# TCAN1146_PWR_MGMT.net
KiCad netlist of a schematic drawn in Altium Designer
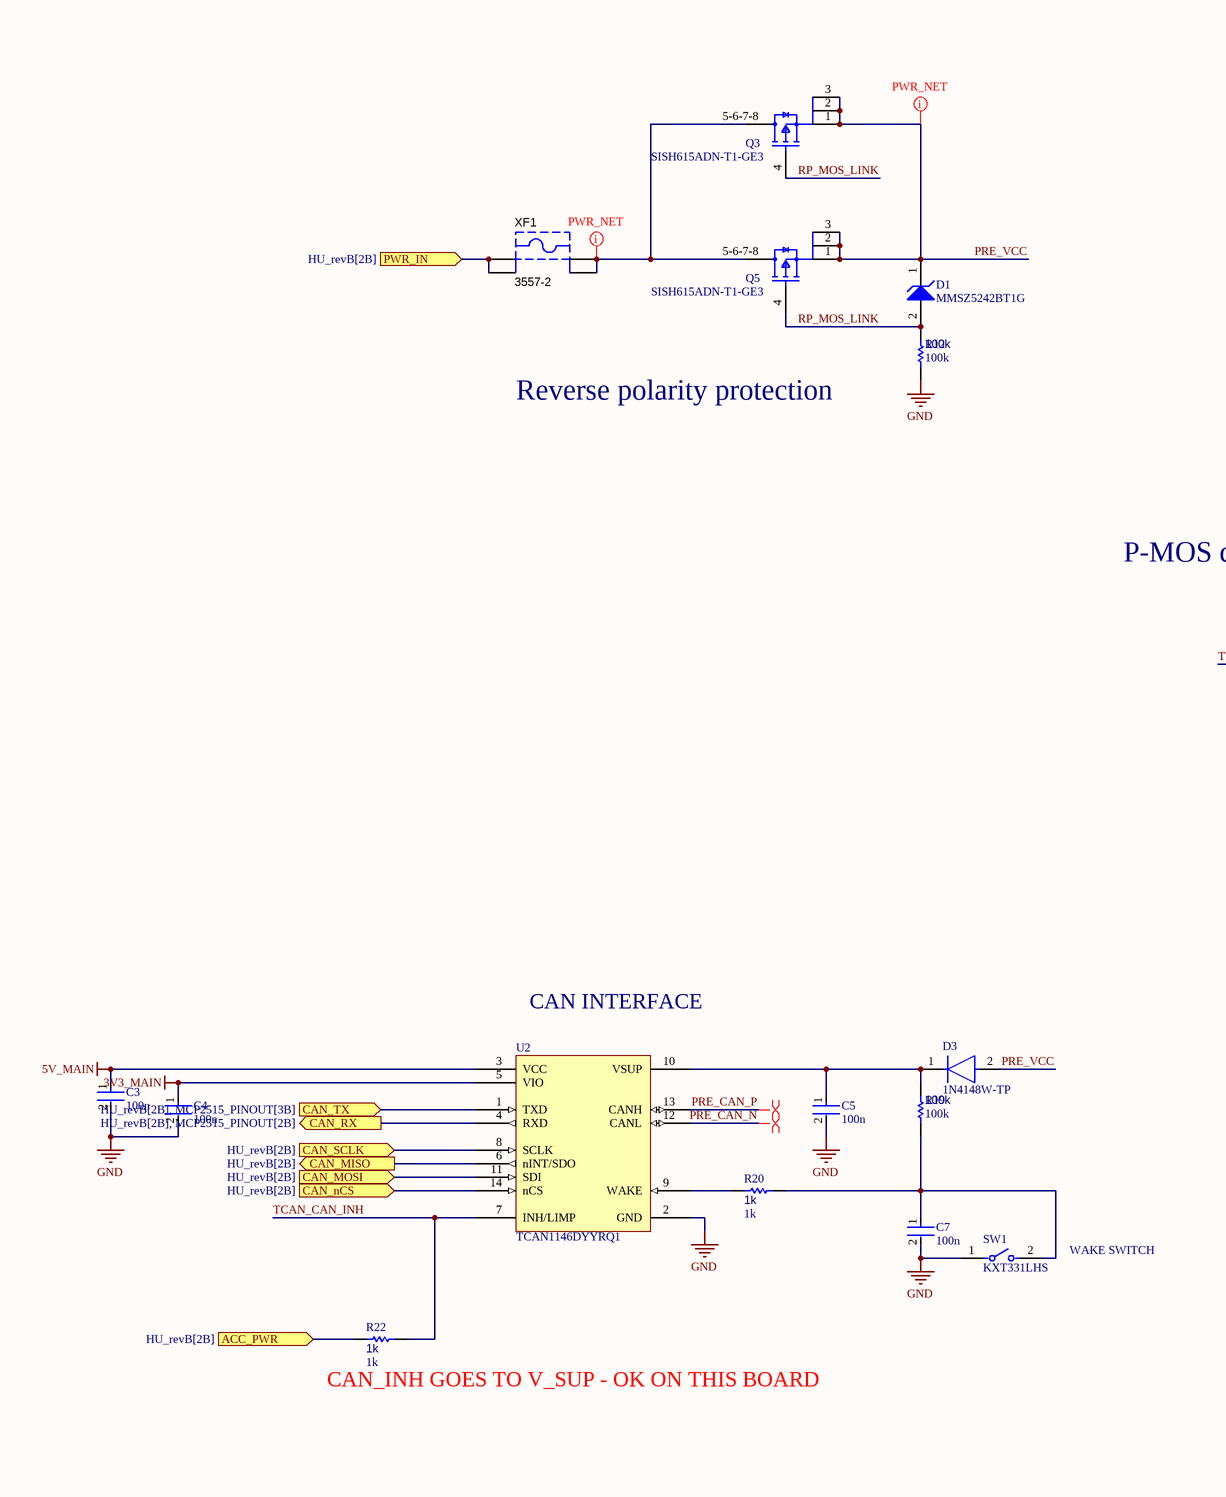
[diagram p0: TCAN1146_PWR_MGMT.SchDoc, left]
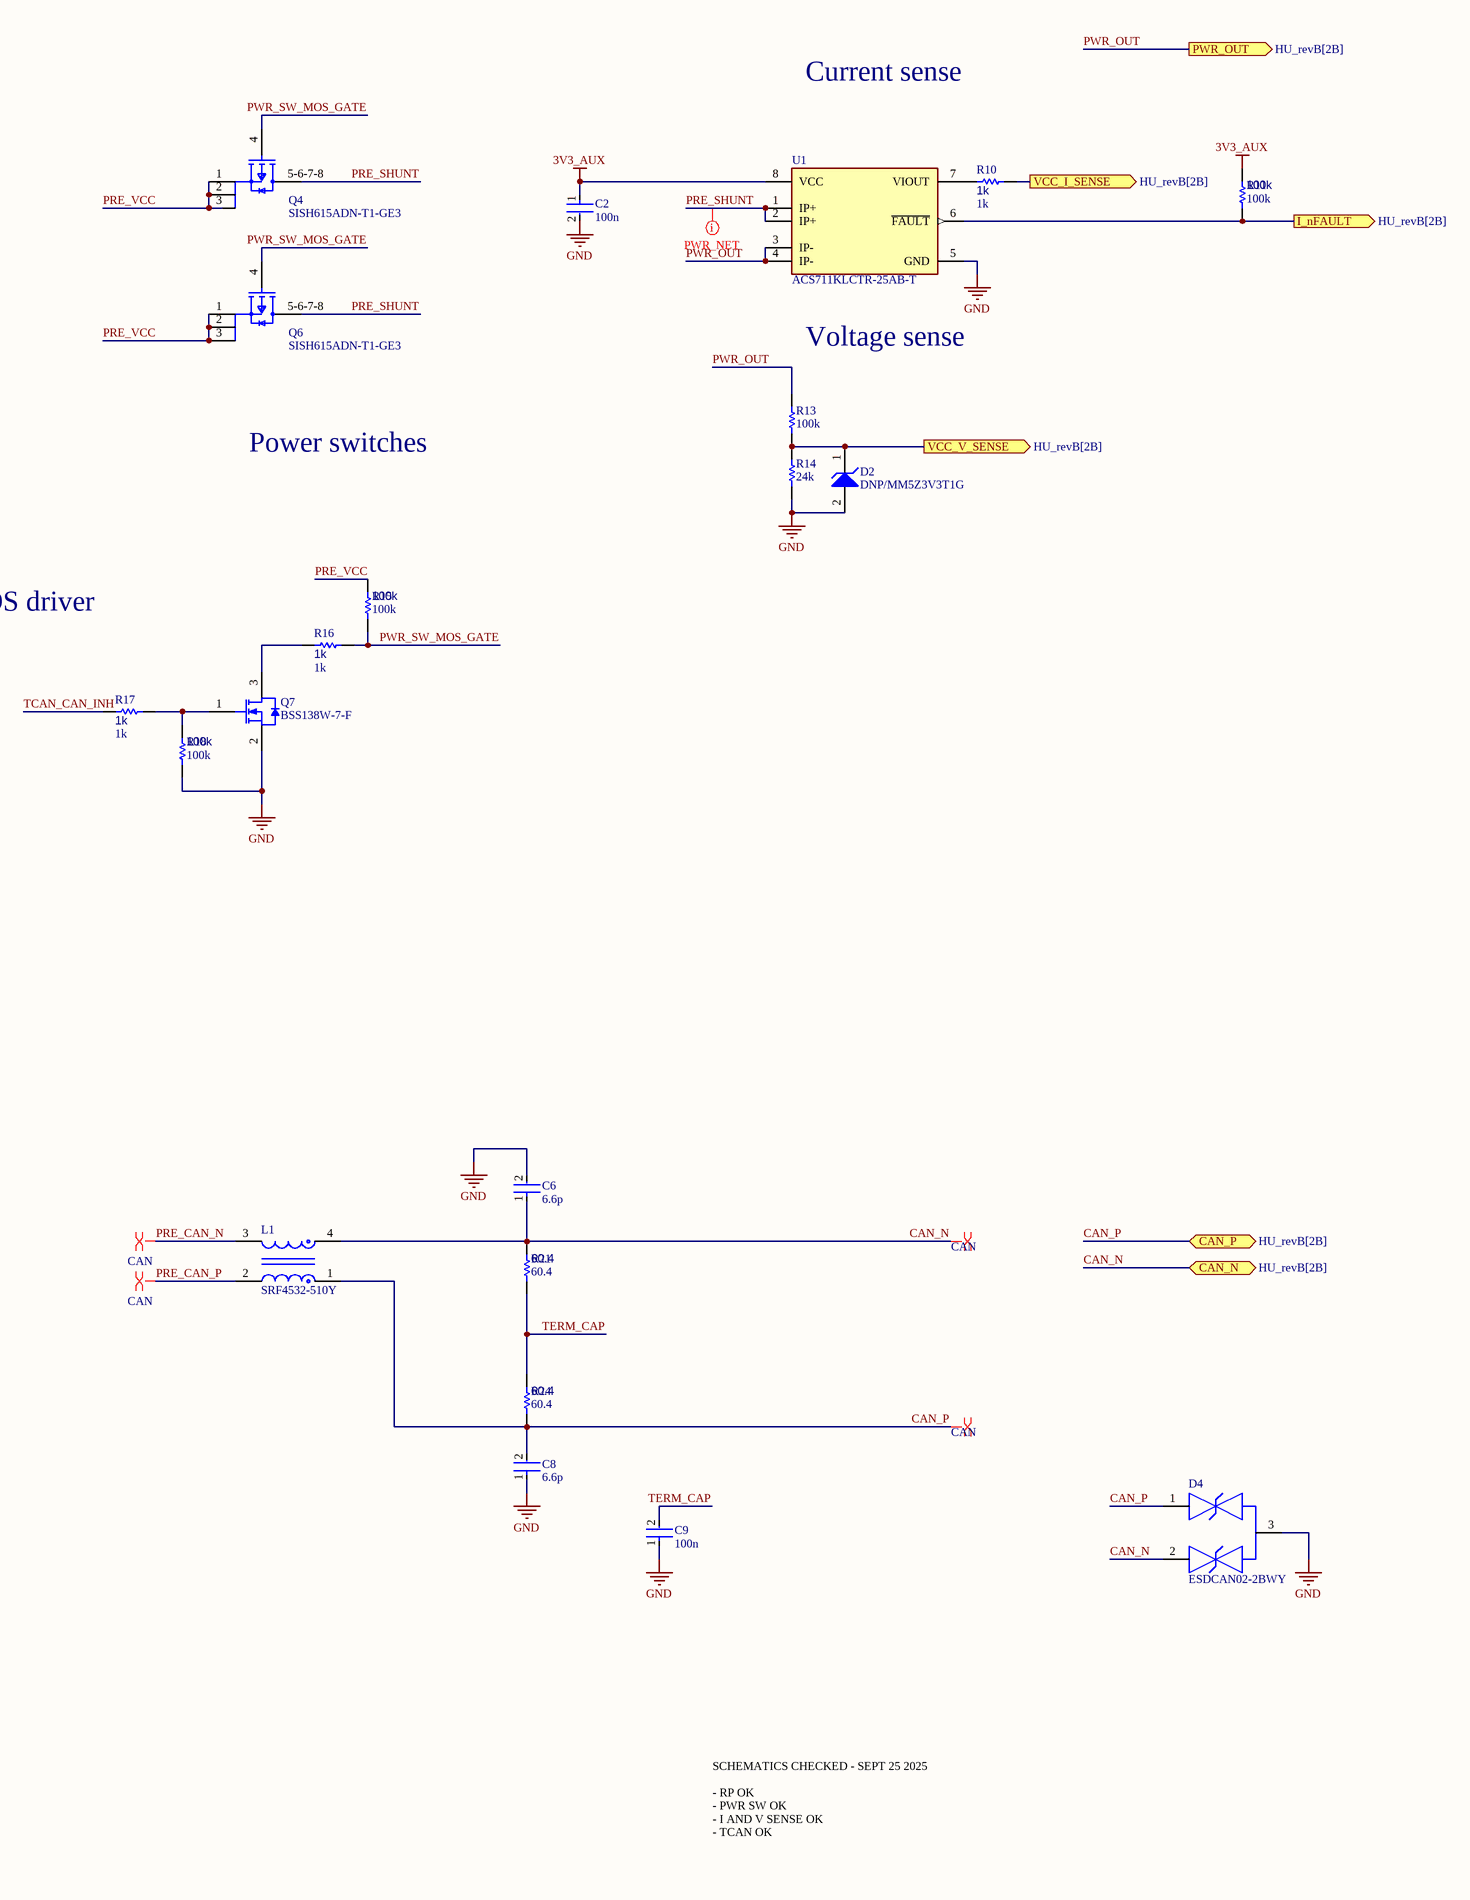
[diagram p1: TCAN1146_PWR_MGMT.SchDoc, right]

(export (version "E")
  (design (tool "Eeschema 10.0.6"))
  (components
    (comp (ref "C2")
      (value "100n")
      (footprint "FP-0402-L_1_0_0_05-W_0_5-IPC_A")
      (description "LARGE PADS, 0402 CAP, CHANGE COMMENT TO MATCH REAL P/N")
      (libsource (lib "Space Concordia") (part "b4654b650e69147ec39a6b967a45e02"))
    )
    (comp (ref "C3")
      (value "100n")
      (footprint "FP-0402-L_1_0_0_05-W_0_5-IPC_A")
      (description "LARGE PADS, 0402 CAP, CHANGE COMMENT TO MATCH REAL P/N")
      (libsource (lib "Space Concordia") (part "b4654b650e69147ec39a6b967a45e02"))
    )
    (comp (ref "C4")
      (value "100n")
      (footprint "FP-0402-L_1_0_0_05-W_0_5-IPC_A")
      (description "LARGE PADS, 0402 CAP, CHANGE COMMENT TO MATCH REAL P/N")
      (libsource (lib "Space Concordia") (part "b4654b650e69147ec39a6b967a45e02"))
    )
    (comp (ref "C5")
      (value "100n")
      (footprint "FP-0402-L_1_0_0_05-W_0_5-IPC_A")
      (description "LARGE PADS, 0402 CAP, CHANGE COMMENT TO MATCH REAL P/N")
      (libsource (lib "Space Concordia") (part "b4654b650e69147ec39a6b967a45e02"))
    )
    (comp (ref "C6")
      (value "6.6p")
      (footprint "FP-0402-L_1_0_0_05-W_0_5-IPC_A")
      (description "LARGE PADS, 0402 CAP, CHANGE COMMENT TO MATCH REAL P/N")
      (libsource (lib "Space Concordia") (part "b4654b650e69147ec39a6b967a45e02"))
    )
    (comp (ref "C7")
      (value "100n")
      (footprint "FP-0402-L_1_0_0_05-W_0_5-IPC_A")
      (description "LARGE PADS, 0402 CAP, CHANGE COMMENT TO MATCH REAL P/N")
      (libsource (lib "Space Concordia") (part "b4654b650e69147ec39a6b967a45e02"))
    )
    (comp (ref "C8")
      (value "6.6p")
      (footprint "FP-0402-L_1_0_0_05-W_0_5-IPC_A")
      (description "LARGE PADS, 0402 CAP, CHANGE COMMENT TO MATCH REAL P/N")
      (libsource (lib "Space Concordia") (part "b4654b650e69147ec39a6b967a45e02"))
    )
    (comp (ref "C9")
      (value "100n")
      (footprint "FP-0402-L_1_0_0_05-W_0_5-IPC_A")
      (description "LARGE PADS, 0402 CAP, CHANGE COMMENT TO MATCH REAL P/N")
      (libsource (lib "Space Concordia") (part "b4654b650e69147ec39a6b967a45e02"))
    )
    (comp (ref "D1")
      (value "MMSZ5242BT1G")
      (footprint "ONSC-SOD-123-2-425-04_V")
      (description "Zener Voltage Regulator, 500 mW, 2-Pin SOD-123, Pb-Free, Tape and Reel")
      (fields (field (name "MANUFACTURER") "On Semiconductor"))
      (libsource (lib "Altium Content Vault") (part "ONSC-K1A2-2"))
    )
    (comp (ref "D2")
      (value "DNP/MM5Z3V3T1G")
      (footprint "ONSC-SOD-523-2-502-01_V")
      (description "Zener Voltage Regulator, 500 mW, 2-Pin SOD-523, Pb-Free, Tape and Reel")
      (fields (field (name "MANUFACTURER") "On Semiconductor") (field (name "PARTNUMBER") "MM5Z3V3T1G"))
      (libsource (lib "Altium Content Vault") (part "ONSC-K1A2-2"))
    )
    (comp (ref "D3")
      (value "1N4148W-TP")
      (footprint "FP-SOD-123-IPC_A")
      (description "DIODE GEN PURP 100V 150MA SOD123")
      (libsource (lib "Altium Content Vault") (part "d7152d700b627762746794eb795d46e"))
    )
    (comp (ref "D4")
      (value "ESDCAN02-2BWY")
      (footprint "FP-SOT323-3L-MFG")
      (description "TVS DIODE 26.5V 44V SOT323-3")
      (fields
        (field (name "MANUFACTURER") "STMicroelectronics")
        (field (name "OCTOPART") "https://octopart.com/esdcan02-2bwy-stmicroelectronics-58631133")
      )
      (libsource (lib "Altium Content Vault") (part "0b9019fb5e52ed66df21ec1535be59d"))
    )
    (comp (ref "L1")
      (value "SRF4532-510Y")
      (footprint "FP-SRF4532-MFG")
      (description "CMC 51UH 200MA 2LN 2KOHM SMD")
      (fields (field (name "TOLERANCE") "50%"))
      (libsource (lib "Altium Content Vault") (part "aca3f6a10b859f211cca95010157f3b"))
    )
    (comp (ref "Q3")
      (value "SISH615ADN-T1-GE3")
      (footprint "SISH615ADN-T1-GE3-Footprint-1")
      (description "Trans MOSFET P-CH 20V 22.1A 8-Pin PowerPAK 1212 EP T/R")
      (libsource (lib "Space Concordia") (part "CMP-013-00036-4"))
    )
    (comp (ref "Q4")
      (value "SISH615ADN-T1-GE3")
      (footprint "SISH615ADN-T1-GE3-Footprint-1")
      (description "Trans MOSFET P-CH 20V 22.1A 8-Pin PowerPAK 1212 EP T/R")
      (libsource (lib "Space Concordia") (part "CMP-013-00036-4"))
    )
    (comp (ref "Q5")
      (value "SISH615ADN-T1-GE3")
      (footprint "SISH615ADN-T1-GE3-Footprint-1")
      (description "Trans MOSFET P-CH 20V 22.1A 8-Pin PowerPAK 1212 EP T/R")
      (libsource (lib "Space Concordia") (part "CMP-013-00036-4"))
    )
    (comp (ref "Q6")
      (value "SISH615ADN-T1-GE3")
      (footprint "SISH615ADN-T1-GE3-Footprint-1")
      (description "Trans MOSFET P-CH 20V 22.1A 8-Pin PowerPAK 1212 EP T/R")
      (libsource (lib "Space Concordia") (part "CMP-013-00036-4"))
    )
    (comp (ref "Q7")
      (value "BSS138W-7-F")
      (footprint "DIOD-SOT323-3_V")
      (fields (field (name "MANUFACTURER") "DiodesIncorporated"))
      (libsource (lib "Altium Content Vault") (part "NEMOS-GSD-3"))
    )
    (comp (ref "R10")
      (value "1k")
      (footprint "R0603B")
      (description "Resistor")
      (fields (field (name "ALTIUM_VALUE") "1k"))
      (libsource (lib "Space Concordia") (part "Resistor"))
    )
    (comp (ref "R11")
      (value "100k")
      (footprint "R0603B")
      (description "Resistor")
      (fields (field (name "ALTIUM_VALUE") "100k"))
      (libsource (lib "Space Concordia") (part "Resistor"))
    )
    (comp (ref "R12")
      (value "100k")
      (footprint "R0603B")
      (description "Resistor")
      (fields (field (name "ALTIUM_VALUE") "100k"))
      (libsource (lib "Space Concordia") (part "Resistor"))
    )
    (comp (ref "R13")
      (value "100k")
      (footprint "R0603B")
      (description "Resistor")
      (libsource (lib "Space Concordia") (part "Resistor"))
    )
    (comp (ref "R14")
      (value "24k")
      (footprint "R0603B")
      (description "Resistor")
      (libsource (lib "Space Concordia") (part "Resistor"))
    )
    (comp (ref "R15")
      (value "100k")
      (footprint "R0603B")
      (description "Resistor")
      (fields (field (name "ALTIUM_VALUE") "100k"))
      (libsource (lib "Space Concordia") (part "Resistor"))
    )
    (comp (ref "R16")
      (value "1k")
      (footprint "R0603B")
      (description "Resistor")
      (fields (field (name "ALTIUM_VALUE") "1k"))
      (libsource (lib "Space Concordia") (part "Resistor"))
    )
    (comp (ref "R17")
      (value "1k")
      (footprint "R0603B")
      (description "Resistor")
      (fields (field (name "ALTIUM_VALUE") "1k"))
      (libsource (lib "Space Concordia") (part "Resistor"))
    )
    (comp (ref "R18")
      (value "100k")
      (footprint "R0603B")
      (description "Resistor")
      (fields (field (name "ALTIUM_VALUE") "100k"))
      (libsource (lib "Space Concordia") (part "Resistor"))
    )
    (comp (ref "R19")
      (value "100k")
      (footprint "R0603B")
      (description "Resistor")
      (fields (field (name "ALTIUM_VALUE") "100k"))
      (libsource (lib "Space Concordia") (part "Resistor"))
    )
    (comp (ref "R20")
      (value "1k")
      (footprint "R0603B")
      (description "Resistor")
      (fields (field (name "ALTIUM_VALUE") "1k"))
      (libsource (lib "Space Concordia") (part "Resistor"))
    )
    (comp (ref "R21")
      (value "60.4")
      (footprint "R0603B")
      (description "Resistor")
      (fields (field (name "ALTIUM_VALUE") "60.4"))
      (libsource (lib "Space Concordia") (part "Resistor"))
    )
    (comp (ref "R22")
      (value "1k")
      (footprint "R0603B")
      (description "Resistor")
      (fields (field (name "ALTIUM_VALUE") "1k"))
      (libsource (lib "Space Concordia") (part "Resistor"))
    )
    (comp (ref "R24")
      (value "60.4")
      (footprint "R0603B")
      (description "Resistor")
      (fields (field (name "ALTIUM_VALUE") "60.4"))
      (libsource (lib "Space Concordia") (part "Resistor"))
    )
    (comp (ref "SW1")
      (value "KXT331LHS")
      (footprint "FP-KXT331LHS-MFG")
      (description "SWITCH TACTILE SPST-NO 0.02A 15V")
      (libsource (lib "Altium Content Vault") (part "bb27bde45df87f1f469753f287ef5ae"))
    )
    (comp (ref "U1")
      (value "ACS711KLCTR-25AB-T")
      (footprint "FP-LC-8-IPC_A")
      (description "SENSOR CURRENT HALL 25A AC/DC")
      (libsource (lib "Altium Content Vault") (part "eeba3158841281b4ae542a6e24976ab"))
    )
    (comp (ref "U2")
      (value "TCAN1146DYYRQ1")
      (footprint "TCAN1146DYYRQ1-Footprint-1")
      (libsource (lib "Space Concordia") (part "CMP-015-00012-2"))
    )
    (comp (ref "XF1")
      (value "3557-2")
      (footprint "KSTN-3557-2")
      (description "FUSE HOLDER, PCB MOUNT, 500VAC, 20A, ROHS")
      (fields (field (name "VOLTAGE") "500V") (field (name "MANUFACTURER") "Keystone-Electronics"))
      (libsource (lib "Altium Content Vault") (part "FUSE_HOLDER-4"))
    )
  )
  (nets
    (net (code "1") (name "/ACC_PWR") (class "Default")
      (node (ref "R22") (pin "1") (pinfunction "1_1") (pintype "passive"))
    )
    (net (code "2") (name "/CAN_MISO") (class "Default")
      (node (ref "U2") (pin "6") (pinfunction "nINT/SDO_6") (pintype "output"))
    )
    (net (code "3") (name "/CAN_MOSI") (class "Default")
      (node (ref "U2") (pin "11") (pinfunction "SDI_11") (pintype "input"))
    )
    (net (code "4") (name "/CAN_N") (class "Default")
      (node (ref "C6") (pin "1") (pinfunction "1_1") (pintype "passive"))
      (node (ref "D4") (pin "2") (pinfunction "2_2") (pintype "passive"))
      (node (ref "L1") (pin "4") (pinfunction "4_4") (pintype "passive"))
      (node (ref "R21") (pin "2") (pinfunction "2_2") (pintype "passive"))
    )
    (net (code "5") (name "/CAN_P") (class "Default")
      (node (ref "C8") (pin "2") (pinfunction "2_2") (pintype "passive"))
      (node (ref "D4") (pin "1") (pinfunction "1_1") (pintype "passive"))
      (node (ref "L1") (pin "1") (pinfunction "1_1") (pintype "passive"))
      (node (ref "R24") (pin "1") (pinfunction "1_1") (pintype "passive"))
    )
    (net (code "6") (name "/CAN_RX") (class "Default")
      (node (ref "U2") (pin "4") (pinfunction "RXD_4") (pintype "output"))
    )
    (net (code "7") (name "/CAN_SCLK") (class "Default")
      (node (ref "U2") (pin "8") (pinfunction "SCLK_8") (pintype "input"))
    )
    (net (code "8") (name "/CAN_TX") (class "Default")
      (node (ref "U2") (pin "1") (pinfunction "TXD_1") (pintype "input"))
    )
    (net (code "9") (name "/CAN_nCS") (class "Default")
      (node (ref "U2") (pin "14") (pinfunction "nCS_14") (pintype "input"))
    )
    (net (code "10") (name "/I_nFAULT") (class "Default")
      (node (ref "R11") (pin "1") (pinfunction "1_1") (pintype "passive"))
      (node (ref "U1") (pin "6") (pinfunction "~{FAULT}_6") (pintype "output"))
    )
    (net (code "11") (name "/PRE_CAN_N") (class "Default")
      (node (ref "L1") (pin "3") (pinfunction "3_3") (pintype "passive"))
      (node (ref "U2") (pin "12") (pinfunction "CANL_12") (pintype "bidirectional"))
    )
    (net (code "12") (name "/PRE_CAN_P") (class "Default")
      (node (ref "L1") (pin "2") (pinfunction "2_2") (pintype "passive"))
      (node (ref "U2") (pin "13") (pinfunction "CANH_13") (pintype "bidirectional"))
    )
    (net (code "13") (name "/PRE_SHUNT") (class "Default")
      (node (ref "Q4") (pin "5-6-7-8") (pinfunction "D_5-6-7-8") (pintype "passive"))
      (node (ref "Q6") (pin "5-6-7-8") (pinfunction "D_5-6-7-8") (pintype "passive"))
      (node (ref "U1") (pin "1") (pinfunction "IP+_1") (pintype "passive"))
      (node (ref "U1") (pin "2") (pinfunction "IP+_2") (pintype "passive"))
    )
    (net (code "14") (name "/PRE_VCC") (class "Default")
      (node (ref "D1") (pin "1") (pinfunction "K_1") (pintype "passive"))
      (node (ref "D3") (pin "2") (pinfunction "A_2") (pintype "passive"))
      (node (ref "Q3") (pin "1") (pinfunction "S_1") (pintype "passive"))
      (node (ref "Q3") (pin "2") (pinfunction "S_2") (pintype "passive"))
      (node (ref "Q3") (pin "3") (pinfunction "S_3") (pintype "passive"))
      (node (ref "Q4") (pin "1") (pinfunction "S_1") (pintype "passive"))
      (node (ref "Q4") (pin "2") (pinfunction "S_2") (pintype "passive"))
      (node (ref "Q4") (pin "3") (pinfunction "S_3") (pintype "passive"))
      (node (ref "Q5") (pin "1") (pinfunction "S_1") (pintype "passive"))
      (node (ref "Q5") (pin "2") (pinfunction "S_2") (pintype "passive"))
      (node (ref "Q5") (pin "3") (pinfunction "S_3") (pintype "passive"))
      (node (ref "Q6") (pin "1") (pinfunction "S_1") (pintype "passive"))
      (node (ref "Q6") (pin "2") (pinfunction "S_2") (pintype "passive"))
      (node (ref "Q6") (pin "3") (pinfunction "S_3") (pintype "passive"))
      (node (ref "R15") (pin "2") (pinfunction "2_2") (pintype "passive"))
    )
    (net (code "15") (name "/PWR_IN") (class "Default")
      (node (ref "XF1") (pin "1") (pinfunction "1_1") (pintype "passive"))
      (node (ref "XF1") (pin "2") (pinfunction "2_2") (pintype "passive"))
    )
    (net (code "16") (name "/PWR_OUT") (class "Default")
      (node (ref "R13") (pin "2") (pinfunction "2_2") (pintype "passive"))
      (node (ref "U1") (pin "3") (pinfunction "IP-_3") (pintype "passive"))
      (node (ref "U1") (pin "4") (pinfunction "IP-_4") (pintype "passive"))
    )
    (net (code "17") (name "/PWR_SW_MOS_GATE") (class "Default")
      (node (ref "Q4") (pin "4") (pinfunction "G_4") (pintype "passive"))
      (node (ref "Q6") (pin "4") (pinfunction "G_4") (pintype "passive"))
      (node (ref "R15") (pin "1") (pinfunction "1_1") (pintype "passive"))
      (node (ref "R16") (pin "2") (pinfunction "2_2") (pintype "passive"))
    )
    (net (code "18") (name "/RP_MOS_LINK") (class "Default")
      (node (ref "D1") (pin "2") (pinfunction "A_2") (pintype "passive"))
      (node (ref "Q3") (pin "4") (pinfunction "G_4") (pintype "passive"))
      (node (ref "Q5") (pin "4") (pinfunction "G_4") (pintype "passive"))
      (node (ref "R12") (pin "2") (pinfunction "2_2") (pintype "passive"))
    )
    (net (code "19") (name "/TCAN_CAN_INH") (class "Default")
      (node (ref "R17") (pin "1") (pinfunction "1_1") (pintype "passive"))
      (node (ref "R22") (pin "2") (pinfunction "2_2") (pintype "passive"))
      (node (ref "U2") (pin "7") (pinfunction "INH/LIMP_7") (pintype "passive"))
    )
    (net (code "20") (name "/TERM_CAP") (class "Default")
      (node (ref "C9") (pin "2") (pinfunction "2_2") (pintype "passive"))
      (node (ref "R21") (pin "1") (pinfunction "1_1") (pintype "passive"))
      (node (ref "R24") (pin "2") (pinfunction "2_2") (pintype "passive"))
    )
    (net (code "21") (name "/VCC_I_SENSE") (class "Default")
      (node (ref "R10") (pin "1") (pinfunction "1_1") (pintype "passive"))
    )
    (net (code "22") (name "/VCC_V_SENSE") (class "Default")
      (node (ref "D2") (pin "1") (pinfunction "K_1") (pintype "passive"))
      (node (ref "R13") (pin "1") (pinfunction "1_1") (pintype "passive"))
      (node (ref "R14") (pin "2") (pinfunction "2_2") (pintype "passive"))
    )
    (net (code "23") (name "3V3_AUX") (class "Default")
      (node (ref "C2") (pin "1") (pinfunction "1_1") (pintype "passive"))
      (node (ref "R11") (pin "2") (pinfunction "2_2") (pintype "passive"))
      (node (ref "U1") (pin "8") (pinfunction "VCC_8") (pintype "power_in"))
    )
    (net (code "24") (name "3V3_MAIN") (class "Default")
      (node (ref "C4") (pin "1") (pinfunction "1_1") (pintype "passive"))
      (node (ref "U2") (pin "5") (pinfunction "VIO_5") (pintype "power_in"))
    )
    (net (code "25") (name "5V_MAIN") (class "Default")
      (node (ref "C3") (pin "1") (pinfunction "1_1") (pintype "passive"))
      (node (ref "U2") (pin "3") (pinfunction "VCC_3") (pintype "power_in"))
    )
    (net (code "26") (name "GND") (class "Default")
      (node (ref "C2") (pin "2") (pinfunction "2_2") (pintype "passive"))
      (node (ref "C3") (pin "2") (pinfunction "2_2") (pintype "passive"))
      (node (ref "C4") (pin "2") (pinfunction "2_2") (pintype "passive"))
      (node (ref "C5") (pin "2") (pinfunction "2_2") (pintype "passive"))
      (node (ref "C6") (pin "2") (pinfunction "2_2") (pintype "passive"))
      (node (ref "C7") (pin "2") (pinfunction "2_2") (pintype "passive"))
      (node (ref "C8") (pin "1") (pinfunction "1_1") (pintype "passive"))
      (node (ref "C9") (pin "1") (pinfunction "1_1") (pintype "passive"))
      (node (ref "D2") (pin "2") (pinfunction "A_2") (pintype "passive"))
      (node (ref "D4") (pin "3") (pinfunction "3_3") (pintype "passive"))
      (node (ref "Q7") (pin "2") (pinfunction "S_2") (pintype "passive"))
      (node (ref "R12") (pin "1") (pinfunction "1_1") (pintype "passive"))
      (node (ref "R14") (pin "1") (pinfunction "1_1") (pintype "passive"))
      (node (ref "R18") (pin "1") (pinfunction "1_1") (pintype "passive"))
      (node (ref "SW1") (pin "1") (pinfunction "1_1") (pintype "passive"))
      (node (ref "U1") (pin "5") (pinfunction "GND_5") (pintype "power_in"))
      (node (ref "U2") (pin "2") (pinfunction "GND_2") (pintype "power_in"))
    )
    (net (code "27") (name "Net-(C7-Pad1)") (class "Default")
      (node (ref "C7") (pin "1") (pinfunction "1_1") (pintype "passive"))
      (node (ref "R19") (pin "1") (pinfunction "1_1") (pintype "passive"))
      (node (ref "R20") (pin "2") (pinfunction "2_2") (pintype "passive"))
      (node (ref "SW1") (pin "2") (pinfunction "2_2") (pintype "passive"))
    )
    (net (code "28") (name "Net-(D3-C)") (class "Default")
      (node (ref "C5") (pin "1") (pinfunction "1_1") (pintype "passive"))
      (node (ref "D3") (pin "1") (pinfunction "C_1") (pintype "passive"))
      (node (ref "R19") (pin "2") (pinfunction "2_2") (pintype "passive"))
      (node (ref "U2") (pin "10") (pinfunction "VSUP_10") (pintype "power_in"))
    )
    (net (code "29") (name "Net-(Q3-D)") (class "Default")
      (node (ref "Q3") (pin "5-6-7-8") (pinfunction "D_5-6-7-8") (pintype "passive"))
      (node (ref "Q5") (pin "5-6-7-8") (pinfunction "D_5-6-7-8") (pintype "passive"))
      (node (ref "XF1") (pin "3") (pinfunction "3_3") (pintype "passive"))
      (node (ref "XF1") (pin "4") (pinfunction "4_4") (pintype "passive"))
    )
    (net (code "30") (name "Net-(Q7-D)") (class "Default")
      (node (ref "Q7") (pin "3") (pinfunction "D_3") (pintype "passive"))
      (node (ref "R16") (pin "1") (pinfunction "1_1") (pintype "passive"))
    )
    (net (code "31") (name "Net-(Q7-G)") (class "Default")
      (node (ref "Q7") (pin "1") (pinfunction "G_1") (pintype "passive"))
      (node (ref "R17") (pin "2") (pinfunction "2_2") (pintype "passive"))
      (node (ref "R18") (pin "2") (pinfunction "2_2") (pintype "passive"))
    )
    (net (code "32") (name "Net-(U1-VIOUT)") (class "Default")
      (node (ref "R10") (pin "2") (pinfunction "2_2") (pintype "passive"))
      (node (ref "U1") (pin "7") (pinfunction "VIOUT_7") (pintype "passive"))
    )
    (net (code "33") (name "Net-(U2-WAKE)") (class "Default")
      (node (ref "R20") (pin "1") (pinfunction "1_1") (pintype "passive"))
      (node (ref "U2") (pin "9") (pinfunction "WAKE_9") (pintype "input"))
    )
  )
)
